# RPi_Zero_W_Breakout_1_1.net
KiCad netlist of a schematic drawn in EAGLE
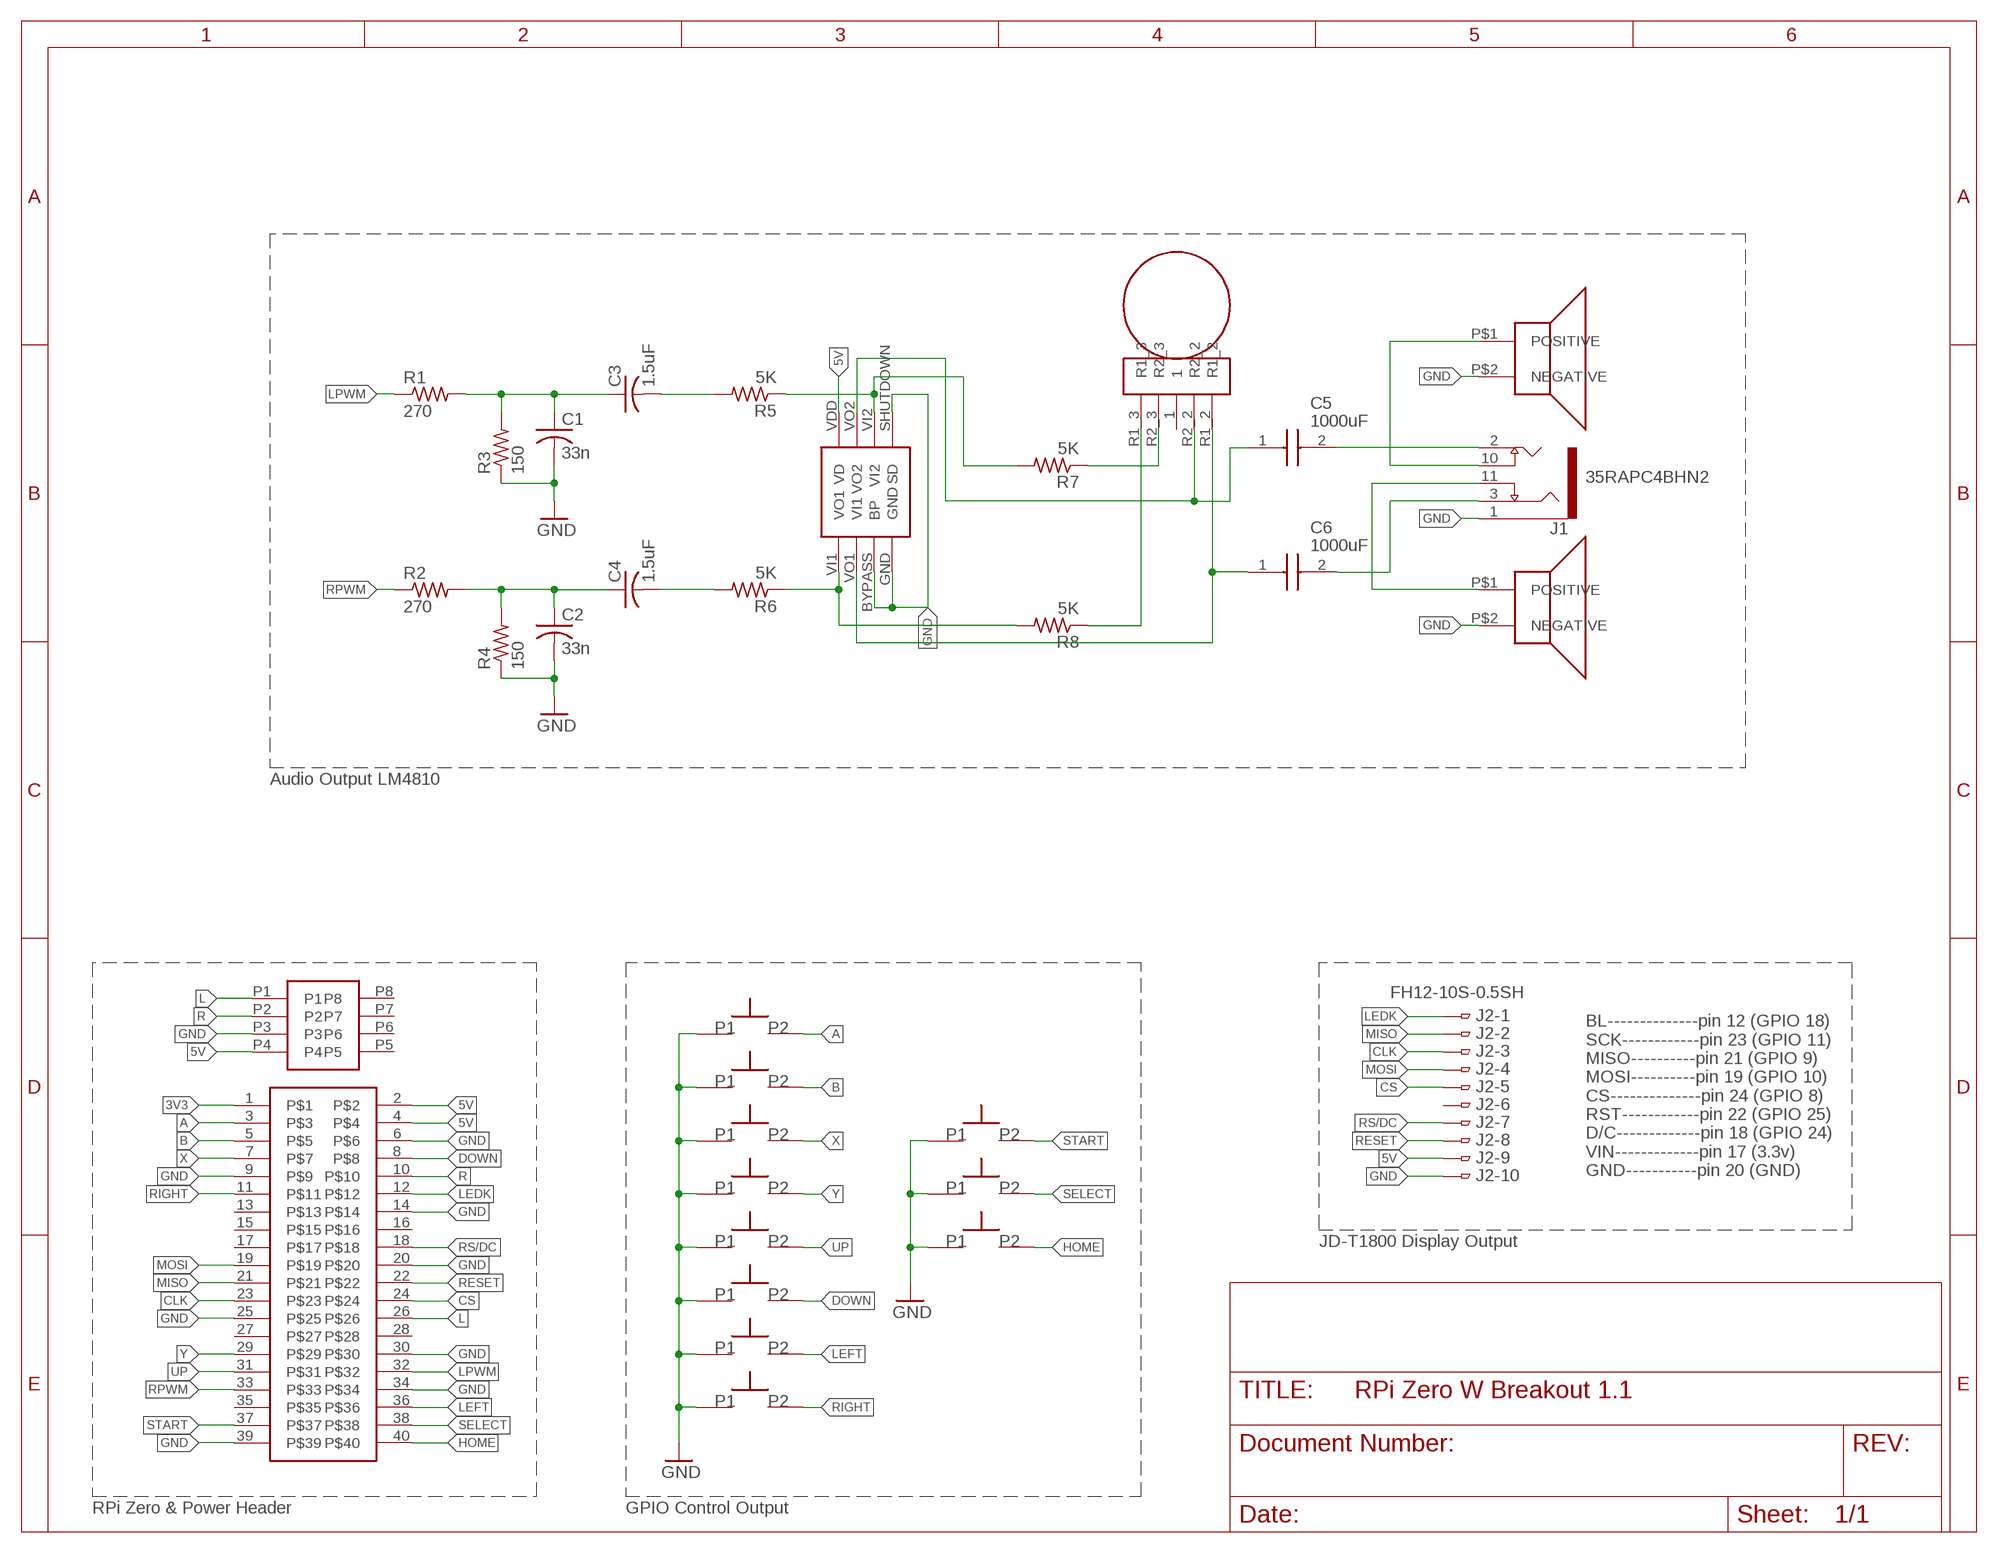
[diagram p0: schematic, sheet 1]

(export (version "E")
  (design (tool "Eeschema 10.0.6"))
  (components
    (comp (ref "A")
      (value "SPST_TACTILE_SWITCH")
      (footprint "eagle-import:SPST_TACTILESWITCH_TL3301PF160QG")
      (libsource (lib "eagle-import") (part "SPST_TACTILE_SWITCH"))
    )
    (comp (ref "B")
      (value "SPST_TACTILESWITCH_TL3301PF160QG")
      (footprint "eagle-import:SPST_TACTILESWITCH_TL3301PF160QG")
      (libsource (lib "eagle-import") (part "SPST_TACTILESWITCH_TL3301PF160QG"))
    )
    (comp (ref "C1")
      (value "33n")
      (footprint "eagle-import:C0805K")
      (libsource (lib "eagle-import") (part "C-USC0805K"))
    )
    (comp (ref "C2")
      (value "33n")
      (footprint "eagle-import:C0805K")
      (libsource (lib "eagle-import") (part "C-USC0805K"))
    )
    (comp (ref "C3")
      (value "1.5uF")
      (footprint "eagle-import:C0805K")
      (libsource (lib "eagle-import") (part "C-USC0805K"))
    )
    (comp (ref "C4")
      (value "1.5uF")
      (footprint "eagle-import:C0805K")
      (libsource (lib "eagle-import") (part "C-USC0805K"))
    )
    (comp (ref "C5")
      (value "1000uF")
      (footprint "eagle-import:UWT(8X10)")
      (fields
        (field (name "MANUFACTURER_PART_NUMBER") "UWT0J102MNL1GS")
        (field (name "MOUSER_PART_NUMBER") "647-UWT0J102MNL1S")
      )
      (libsource (lib "eagle-import") (part "UWT0J102MNL1GS"))
    )
    (comp (ref "C6")
      (value "1000uF")
      (footprint "eagle-import:UWT(8X10)")
      (fields
        (field (name "MANUFACTURER_PART_NUMBER") "UWT0J102MNL1GS")
        (field (name "MOUSER_PART_NUMBER") "647-UWT0J102MNL1S")
      )
      (libsource (lib "eagle-import") (part "UWT0J102MNL1GS"))
    )
    (comp (ref "DOWN")
      (value "SPST_TACTILESWITCH_TL3301PF160QG")
      (footprint "eagle-import:SPST_TACTILESWITCH_TL3301PF160QG")
      (libsource (lib "eagle-import") (part "SPST_TACTILESWITCH_TL3301PF160QG"))
    )
    (comp (ref "H1")
      (value "M22-6340442")
      (footprint "eagle-import:M22-6340442")
      (libsource (lib "eagle-import") (part "M22-6340442"))
    )
    (comp (ref "HOME")
      (value "SPST_TACTILESWITCH_TL3301PF160QG")
      (footprint "eagle-import:SPST_TACTILESWITCH_TL3301PF160QG")
      (libsource (lib "eagle-import") (part "SPST_TACTILESWITCH_TL3301PF160QG"))
    )
    (comp (ref "J1")
      (value "35RAPC4BHN2")
      (footprint "eagle-import:SWITCHCRAFT_35RAPC4BHN2")
      (fields (field (name "DIGI-KEY_PART_NUMBER") "SC1459-ND") (field (name "MF") "Switchcraft"))
      (libsource (lib "eagle-import") (part "35RAPC4BHN2"))
    )
    (comp (ref "J2")
      (value "FH12-10S-0.5SH")
      (footprint "eagle-import:FH12-10S-0.5SH")
      (fields (field (name "MPN") "FH12-10S-0.5SH(55)"))
      (libsource (lib "eagle-import") (part "FH12-10S-0.5SH"))
    )
    (comp (ref "LEFT")
      (value "SPST_TACTILESWITCH_TL3301PF160QG")
      (footprint "eagle-import:SPST_TACTILESWITCH_TL3301PF160QG")
      (libsource (lib "eagle-import") (part "SPST_TACTILESWITCH_TL3301PF160QG"))
    )
    (comp (ref "LSPK")
      (value "SP-1208")
      (footprint "eagle-import:SP-1208")
      (libsource (lib "eagle-import") (part "SP-1208"))
    )
    (comp (ref "R1")
      (value "270")
      (footprint "eagle-import:R0805")
      (libsource (lib "eagle-import") (part "R-US_R0805"))
    )
    (comp (ref "R2")
      (value "270")
      (footprint "eagle-import:R0805")
      (libsource (lib "eagle-import") (part "R-US_R0805"))
    )
    (comp (ref "R3")
      (value "150")
      (footprint "eagle-import:R0805")
      (libsource (lib "eagle-import") (part "R-US_R0805"))
    )
    (comp (ref "R4")
      (value "150")
      (footprint "eagle-import:R0805")
      (libsource (lib "eagle-import") (part "R-US_R0805"))
    )
    (comp (ref "R5")
      (value "5K")
      (footprint "eagle-import:R0805")
      (libsource (lib "eagle-import") (part "R-US_R0805"))
    )
    (comp (ref "R6")
      (value "5K")
      (footprint "eagle-import:R0805")
      (libsource (lib "eagle-import") (part "R-US_R0805"))
    )
    (comp (ref "R7")
      (value "5K")
      (footprint "eagle-import:R0805")
      (libsource (lib "eagle-import") (part "R-US_R0805"))
    )
    (comp (ref "R8")
      (value "5K")
      (footprint "eagle-import:R0805")
      (libsource (lib "eagle-import") (part "R-US_R0805"))
    )
    (comp (ref "RF")
      (value "RK14J12A0A0K")
      (footprint "eagle-import:RK14J12A0A0K")
      (libsource (lib "eagle-import") (part "RK14J12A0A0K"))
    )
    (comp (ref "RIGHT")
      (value "SPST_TACTILESWITCH_TL3301PF160QG")
      (footprint "eagle-import:SPST_TACTILESWITCH_TL3301PF160QG")
      (libsource (lib "eagle-import") (part "SPST_TACTILESWITCH_TL3301PF160QG"))
    )
    (comp (ref "RSPK")
      (value "SP-1208")
      (footprint "eagle-import:SP-1208")
      (libsource (lib "eagle-import") (part "SP-1208"))
    )
    (comp (ref "SELECT")
      (value "SPST_TACTILESWITCH_TL3301PF160QG")
      (footprint "eagle-import:SPST_TACTILESWITCH_TL3301PF160QG")
      (libsource (lib "eagle-import") (part "SPST_TACTILESWITCH_TL3301PF160QG"))
    )
    (comp (ref "START")
      (value "SPST_TACTILE_SWITCH")
      (footprint "eagle-import:SPST_TACTILESWITCH_TL3301PF160QG")
      (libsource (lib "eagle-import") (part "SPST_TACTILE_SWITCH"))
    )
    (comp (ref "U$1")
      (value "RPI_ZERO")
      (footprint "eagle-import:RPI_ZERO")
      (libsource (lib "eagle-import") (part "RPI_ZERO"))
    )
    (comp (ref "U$2")
      (value "LM4810MM/NOPBCT-ND")
      (footprint "eagle-import:NOPBCT-ND")
      (libsource (lib "eagle-import") (part "LM4810MM/NOPBCT-ND"))
    )
    (comp (ref "UP")
      (value "SPST_TACTILESWITCH_TL3301PF160QG")
      (footprint "eagle-import:SPST_TACTILESWITCH_TL3301PF160QG")
      (libsource (lib "eagle-import") (part "SPST_TACTILESWITCH_TL3301PF160QG"))
    )
    (comp (ref "X")
      (value "SPST_TACTILESWITCH_TL3301PF160QG")
      (footprint "eagle-import:SPST_TACTILESWITCH_TL3301PF160QG")
      (libsource (lib "eagle-import") (part "SPST_TACTILESWITCH_TL3301PF160QG"))
    )
    (comp (ref "Y")
      (value "SPST_TACTILESWITCH_TL3301PF160QG")
      (footprint "eagle-import:SPST_TACTILESWITCH_TL3301PF160QG")
      (libsource (lib "eagle-import") (part "SPST_TACTILESWITCH_TL3301PF160QG"))
    )
  )
  (nets
    (net (code "1") (name "3V3") (class "Default")
      (node (ref "U$1") (pin "1") (pinfunction "P$1_1") (pintype "bidirectional"))
    )
    (net (code "2") (name "5V") (class "Default")
      (node (ref "H1") (pin "P4") (pinfunction "P4_P4") (pintype "bidirectional"))
      (node (ref "J2") (pin "9") (pinfunction "1_9") (pintype "passive"))
      (node (ref "U$1") (pin "2") (pinfunction "P$2_2") (pintype "bidirectional"))
      (node (ref "U$1") (pin "4") (pinfunction "P$4_4") (pintype "bidirectional"))
      (node (ref "U$2") (pin "VDD") (pinfunction "VD_VDD") (pintype "bidirectional"))
    )
    (net (code "3") (name "A") (class "Default")
      (node (ref "A") (pin "P$3") (pinfunction "P$2_P$3") (pintype "bidirectional"))
      (node (ref "U$1") (pin "3") (pinfunction "P$3_3") (pintype "bidirectional"))
    )
    (net (code "4") (name "B") (class "Default")
      (node (ref "B") (pin "P$3") (pinfunction "P$2_P$3") (pintype "bidirectional"))
      (node (ref "U$1") (pin "5") (pinfunction "P$5_5") (pintype "bidirectional"))
    )
    (net (code "5") (name "CLK") (class "Default")
      (node (ref "J2") (pin "3") (pinfunction "1_3") (pintype "passive"))
      (node (ref "U$1") (pin "23") (pinfunction "P$23_23") (pintype "bidirectional"))
    )
    (net (code "6") (name "CS") (class "Default")
      (node (ref "J2") (pin "5") (pinfunction "1_5") (pintype "passive"))
      (node (ref "U$1") (pin "24") (pinfunction "P$24_24") (pintype "bidirectional"))
    )
    (net (code "7") (name "DOWN") (class "Default")
      (node (ref "DOWN") (pin "P$3") (pinfunction "P$2_P$3") (pintype "bidirectional"))
      (node (ref "U$1") (pin "8") (pinfunction "P$8_8") (pintype "bidirectional"))
    )
    (net (code "8") (name "GND") (class "Default")
      (node (ref "A") (pin "P$1") (pinfunction "P$1_P$1") (pintype "bidirectional"))
      (node (ref "B") (pin "P$1") (pinfunction "P$1_P$1") (pintype "bidirectional"))
      (node (ref "C1") (pin "2") (pinfunction "2_2") (pintype "passive"))
      (node (ref "C2") (pin "2") (pinfunction "2_2") (pintype "passive"))
      (node (ref "DOWN") (pin "P$1") (pinfunction "P$1_P$1") (pintype "bidirectional"))
      (node (ref "H1") (pin "P3") (pinfunction "P3_P3") (pintype "bidirectional"))
      (node (ref "HOME") (pin "P$1") (pinfunction "P$1_P$1") (pintype "bidirectional"))
      (node (ref "J1") (pin "1") (pinfunction "1_1") (pintype "passive"))
      (node (ref "J2") (pin "10") (pinfunction "1_10") (pintype "passive"))
      (node (ref "LEFT") (pin "P$1") (pinfunction "P$1_P$1") (pintype "bidirectional"))
      (node (ref "LSPK") (pin "P$2") (pinfunction "NEGATIVE_P$2") (pintype "bidirectional"))
      (node (ref "R3") (pin "1") (pinfunction "1_1") (pintype "passive"))
      (node (ref "R4") (pin "1") (pinfunction "1_1") (pintype "passive"))
      (node (ref "RIGHT") (pin "P$1") (pinfunction "P$1_P$1") (pintype "bidirectional"))
      (node (ref "RSPK") (pin "P$2") (pinfunction "NEGATIVE_P$2") (pintype "bidirectional"))
      (node (ref "SELECT") (pin "P$1") (pinfunction "P$1_P$1") (pintype "bidirectional"))
      (node (ref "START") (pin "P$1") (pinfunction "P$1_P$1") (pintype "bidirectional"))
      (node (ref "U$1") (pin "14") (pinfunction "P$14_14") (pintype "bidirectional"))
      (node (ref "U$1") (pin "20") (pinfunction "P$20_20") (pintype "bidirectional"))
      (node (ref "U$1") (pin "25") (pinfunction "P$25_25") (pintype "bidirectional"))
      (node (ref "U$1") (pin "30") (pinfunction "P$30_30") (pintype "bidirectional"))
      (node (ref "U$1") (pin "34") (pinfunction "P$34_34") (pintype "bidirectional"))
      (node (ref "U$1") (pin "39") (pinfunction "P$39_39") (pintype "bidirectional"))
      (node (ref "U$1") (pin "6") (pinfunction "P$6_6") (pintype "bidirectional"))
      (node (ref "U$1") (pin "9") (pinfunction "P$9_9") (pintype "bidirectional"))
      (node (ref "U$2") (pin "BYPASS") (pinfunction "BP_BYPASS") (pintype "bidirectional"))
      (node (ref "U$2") (pin "GND") (pinfunction "GND_GND") (pintype "bidirectional"))
      (node (ref "U$2") (pin "SHUTDOWN") (pinfunction "SD_SHUTDOWN") (pintype "bidirectional"))
      (node (ref "UP") (pin "P$1") (pinfunction "P$1_P$1") (pintype "bidirectional"))
      (node (ref "X") (pin "P$1") (pinfunction "P$1_P$1") (pintype "bidirectional"))
      (node (ref "Y") (pin "P$1") (pinfunction "P$1_P$1") (pintype "bidirectional"))
    )
    (net (code "9") (name "HOME") (class "Default")
      (node (ref "HOME") (pin "P$3") (pinfunction "P$2_P$3") (pintype "bidirectional"))
      (node (ref "U$1") (pin "40") (pinfunction "P$40_40") (pintype "bidirectional"))
    )
    (net (code "10") (name "L") (class "Default")
      (node (ref "H1") (pin "P1") (pinfunction "P1_P1") (pintype "bidirectional"))
      (node (ref "U$1") (pin "26") (pinfunction "P$26_26") (pintype "bidirectional"))
    )
    (net (code "11") (name "LEDK") (class "Default")
      (node (ref "J2") (pin "1") (pinfunction "1_1") (pintype "passive"))
      (node (ref "U$1") (pin "12") (pinfunction "P$12_12") (pintype "bidirectional"))
    )
    (net (code "12") (name "LEFT") (class "Default")
      (node (ref "LEFT") (pin "P$3") (pinfunction "P$2_P$3") (pintype "bidirectional"))
      (node (ref "U$1") (pin "36") (pinfunction "P$36_36") (pintype "bidirectional"))
    )
    (net (code "13") (name "LPWM") (class "Default")
      (node (ref "R1") (pin "1") (pinfunction "1_1") (pintype "passive"))
      (node (ref "U$1") (pin "32") (pinfunction "P$32_32") (pintype "bidirectional"))
    )
    (net (code "14") (name "MISO") (class "Default")
      (node (ref "J2") (pin "2") (pinfunction "1_2") (pintype "passive"))
      (node (ref "U$1") (pin "21") (pinfunction "P$21_21") (pintype "bidirectional"))
    )
    (net (code "15") (name "MOSI") (class "Default")
      (node (ref "J2") (pin "4") (pinfunction "1_4") (pintype "passive"))
      (node (ref "U$1") (pin "19") (pinfunction "P$19_19") (pintype "bidirectional"))
    )
    (net (code "16") (name "Net-(C1-Pad1)") (class "Default")
      (node (ref "C1") (pin "1") (pinfunction "1_1") (pintype "passive"))
      (node (ref "C3") (pin "1") (pinfunction "1_1") (pintype "passive"))
      (node (ref "R1") (pin "2") (pinfunction "2_2") (pintype "passive"))
      (node (ref "R3") (pin "2") (pinfunction "2_2") (pintype "passive"))
    )
    (net (code "17") (name "Net-(C2-Pad1)") (class "Default")
      (node (ref "C2") (pin "1") (pinfunction "1_1") (pintype "passive"))
      (node (ref "C4") (pin "1") (pinfunction "1_1") (pintype "passive"))
      (node (ref "R2") (pin "2") (pinfunction "2_2") (pintype "passive"))
      (node (ref "R4") (pin "2") (pinfunction "2_2") (pintype "passive"))
    )
    (net (code "18") (name "Net-(C3-Pad2)") (class "Default")
      (node (ref "C3") (pin "2") (pinfunction "2_2") (pintype "passive"))
      (node (ref "R5") (pin "2") (pinfunction "2_2") (pintype "passive"))
    )
    (net (code "19") (name "Net-(C4-Pad2)") (class "Default")
      (node (ref "C4") (pin "2") (pinfunction "2_2") (pintype "passive"))
      (node (ref "R6") (pin "2") (pinfunction "2_2") (pintype "passive"))
    )
    (net (code "20") (name "Net-(C5-+)") (class "Default")
      (node (ref "C5") (pin "1") (pinfunction "+_1") (pintype "bidirectional"))
      (node (ref "RF") (pin "R2_2") (pinfunction "R2_2_R2_2") (pintype "bidirectional"))
      (node (ref "U$2") (pin "VO2") (pinfunction "VO2_VO2") (pintype "bidirectional"))
    )
    (net (code "21") (name "Net-(C5--)") (class "Default")
      (node (ref "C5") (pin "2") (pinfunction "-_2") (pintype "bidirectional"))
      (node (ref "J1") (pin "2") (pinfunction "2_2") (pintype "passive"))
    )
    (net (code "22") (name "Net-(C6-+)") (class "Default")
      (node (ref "C6") (pin "1") (pinfunction "+_1") (pintype "bidirectional"))
      (node (ref "RF") (pin "R1_2") (pinfunction "R1_2_R1_2") (pintype "bidirectional"))
      (node (ref "U$2") (pin "VO1") (pinfunction "VI1_VO1") (pintype "bidirectional"))
    )
    (net (code "23") (name "Net-(C6--)") (class "Default")
      (node (ref "C6") (pin "2") (pinfunction "-_2") (pintype "bidirectional"))
      (node (ref "J1") (pin "3") (pinfunction "3_3") (pintype "passive"))
    )
    (net (code "24") (name "Net-(LSPK-POSITIVE)") (class "Default")
      (node (ref "J1") (pin "10") (pinfunction "10_10") (pintype "passive"))
      (node (ref "LSPK") (pin "P$1") (pinfunction "POSITIVE_P$1") (pintype "bidirectional"))
    )
    (net (code "25") (name "Net-(R5-Pad1)") (class "Default")
      (node (ref "R5") (pin "1") (pinfunction "1_1") (pintype "passive"))
      (node (ref "R7") (pin "2") (pinfunction "2_2") (pintype "passive"))
      (node (ref "U$2") (pin "VI2") (pinfunction "VI2_VI2") (pintype "bidirectional"))
    )
    (net (code "26") (name "Net-(R7-Pad1)") (class "Default")
      (node (ref "R7") (pin "1") (pinfunction "1_1") (pintype "passive"))
      (node (ref "RF") (pin "R2_3") (pinfunction "R2_3_R2_3") (pintype "bidirectional"))
    )
    (net (code "27") (name "Net-(R8-Pad1)") (class "Default")
      (node (ref "R8") (pin "1") (pinfunction "1_1") (pintype "passive"))
      (node (ref "RF") (pin "R1_3") (pinfunction "R1_3_R1_3") (pintype "bidirectional"))
    )
    (net (code "28") (name "Net-(RSPK-POSITIVE)") (class "Default")
      (node (ref "J1") (pin "11") (pinfunction "11_11") (pintype "passive"))
      (node (ref "RSPK") (pin "P$1") (pinfunction "POSITIVE_P$1") (pintype "bidirectional"))
    )
    (net (code "29") (name "Net-(U$2-VO1)") (class "Default")
      (node (ref "R6") (pin "1") (pinfunction "1_1") (pintype "passive"))
      (node (ref "R8") (pin "2") (pinfunction "2_2") (pintype "passive"))
      (node (ref "U$2") (pin "VI1") (pinfunction "VO1_VI1") (pintype "bidirectional"))
    )
    (net (code "30") (name "R") (class "Default")
      (node (ref "H1") (pin "P2") (pinfunction "P2_P2") (pintype "bidirectional"))
      (node (ref "U$1") (pin "10") (pinfunction "P$10_10") (pintype "bidirectional"))
    )
    (net (code "31") (name "RESET") (class "Default")
      (node (ref "J2") (pin "8") (pinfunction "1_8") (pintype "passive"))
      (node (ref "U$1") (pin "22") (pinfunction "P$22_22") (pintype "bidirectional"))
    )
    (net (code "32") (name "RIGHT") (class "Default")
      (node (ref "RIGHT") (pin "P$3") (pinfunction "P$2_P$3") (pintype "bidirectional"))
      (node (ref "U$1") (pin "11") (pinfunction "P$11_11") (pintype "bidirectional"))
    )
    (net (code "33") (name "RPWM") (class "Default")
      (node (ref "R2") (pin "1") (pinfunction "1_1") (pintype "passive"))
      (node (ref "U$1") (pin "33") (pinfunction "P$33_33") (pintype "bidirectional"))
    )
    (net (code "34") (name "RS{slash}DC") (class "Default")
      (node (ref "J2") (pin "7") (pinfunction "1_7") (pintype "passive"))
      (node (ref "U$1") (pin "18") (pinfunction "P$18_18") (pintype "bidirectional"))
    )
    (net (code "35") (name "SELECT") (class "Default")
      (node (ref "SELECT") (pin "P$3") (pinfunction "P$2_P$3") (pintype "bidirectional"))
      (node (ref "U$1") (pin "38") (pinfunction "P$38_38") (pintype "bidirectional"))
    )
    (net (code "36") (name "START") (class "Default")
      (node (ref "START") (pin "P$3") (pinfunction "P$2_P$3") (pintype "bidirectional"))
      (node (ref "U$1") (pin "37") (pinfunction "P$37_37") (pintype "bidirectional"))
    )
    (net (code "37") (name "UP") (class "Default")
      (node (ref "U$1") (pin "31") (pinfunction "P$31_31") (pintype "bidirectional"))
      (node (ref "UP") (pin "P$3") (pinfunction "P$2_P$3") (pintype "bidirectional"))
    )
    (net (code "38") (name "X") (class "Default")
      (node (ref "U$1") (pin "7") (pinfunction "P$7_7") (pintype "bidirectional"))
      (node (ref "X") (pin "P$3") (pinfunction "P$2_P$3") (pintype "bidirectional"))
    )
    (net (code "39") (name "Y") (class "Default")
      (node (ref "U$1") (pin "29") (pinfunction "P$29_29") (pintype "bidirectional"))
      (node (ref "Y") (pin "P$3") (pinfunction "P$2_P$3") (pintype "bidirectional"))
    )
    (net (code "40") (name "unconnected-(H1-PadP5)") (class "Default")
      (node (ref "H1") (pin "P5") (pinfunction "P5_P5") (pintype "bidirectional"))
    )
    (net (code "41") (name "unconnected-(H1-PadP6)") (class "Default")
      (node (ref "H1") (pin "P6") (pinfunction "P6_P6") (pintype "bidirectional"))
    )
    (net (code "42") (name "unconnected-(H1-PadP7)") (class "Default")
      (node (ref "H1") (pin "P7") (pinfunction "P7_P7") (pintype "bidirectional"))
    )
    (net (code "43") (name "unconnected-(H1-PadP8)") (class "Default")
      (node (ref "H1") (pin "P8") (pinfunction "P8_P8") (pintype "bidirectional"))
    )
    (net (code "44") (name "unconnected-(J2G-1-Pad6)") (class "Default")
      (node (ref "J2") (pin "6") (pinfunction "1_6") (pintype "passive"))
    )
    (net (code "45") (name "unconnected-(RF-Pad1)") (class "Default")
      (node (ref "RF") (pin "1") (pinfunction "1_1") (pintype "bidirectional"))
    )
    (net (code "46") (name "unconnected-(U$1-P$13-Pad13)") (class "Default")
      (node (ref "U$1") (pin "13") (pinfunction "P$13_13") (pintype "bidirectional"))
    )
    (net (code "47") (name "unconnected-(U$1-P$15-Pad15)") (class "Default")
      (node (ref "U$1") (pin "15") (pinfunction "P$15_15") (pintype "bidirectional"))
    )
    (net (code "48") (name "unconnected-(U$1-P$16-Pad16)") (class "Default")
      (node (ref "U$1") (pin "16") (pinfunction "P$16_16") (pintype "bidirectional"))
    )
    (net (code "49") (name "unconnected-(U$1-P$17-Pad17)") (class "Default")
      (node (ref "U$1") (pin "17") (pinfunction "P$17_17") (pintype "bidirectional"))
    )
    (net (code "50") (name "unconnected-(U$1-P$27-Pad27)") (class "Default")
      (node (ref "U$1") (pin "27") (pinfunction "P$27_27") (pintype "bidirectional"))
    )
    (net (code "51") (name "unconnected-(U$1-P$28-Pad28)") (class "Default")
      (node (ref "U$1") (pin "28") (pinfunction "P$28_28") (pintype "bidirectional"))
    )
    (net (code "52") (name "unconnected-(U$1-P$35-Pad35)") (class "Default")
      (node (ref "U$1") (pin "35") (pinfunction "P$35_35") (pintype "bidirectional"))
    )
  )
)
